# Light_SOT32.net
KiCad netlist of a schematic drawn in EAGLE
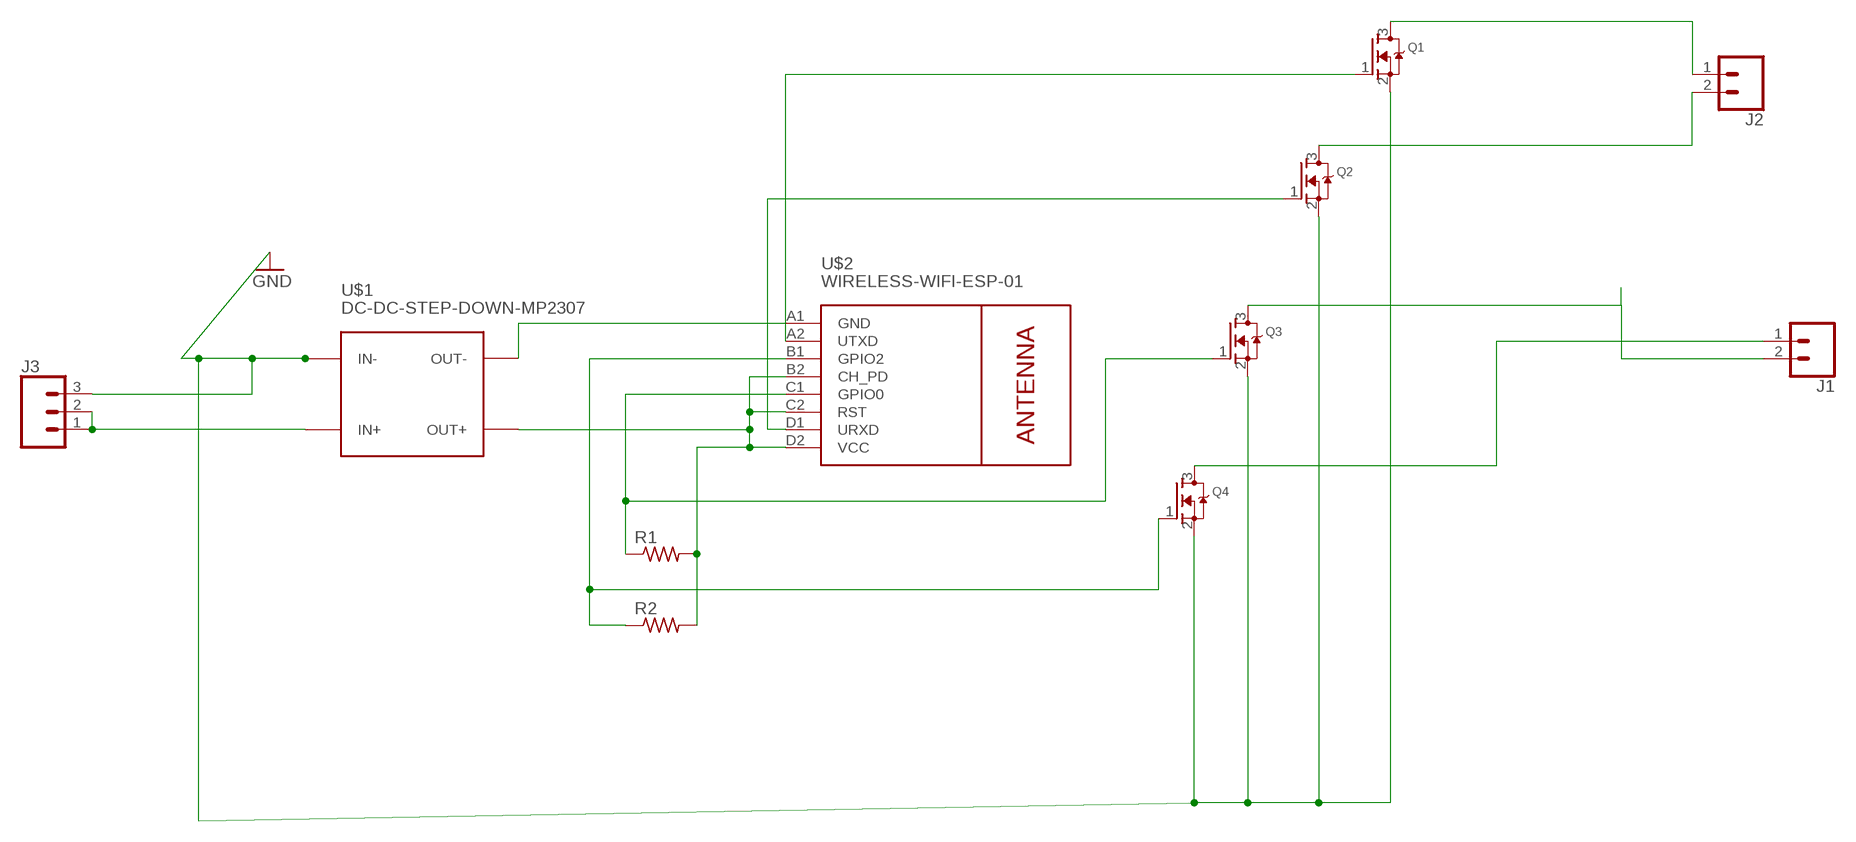
[diagram p0: schematic, sheet 1]

(export (version "E")
  (design (tool "Eeschema 10.0.6"))
  (components
    (comp (ref "J1")
      (value "CONN_023.5MM")
      (footprint "eagle-import:SCREWTERMINAL-3.5MM-2")
      (libsource (lib "eagle-import") (part "CONN_023.5MM"))
    )
    (comp (ref "J2")
      (value "CONN_023.5MM")
      (footprint "eagle-import:SCREWTERMINAL-3.5MM-2")
      (libsource (lib "eagle-import") (part "CONN_023.5MM"))
    )
    (comp (ref "J3")
      (value "CONN_03SCREW")
      (footprint "eagle-import:SCREWTERMINAL-3.5MM-3")
      (libsource (lib "eagle-import") (part "CONN_03SCREW"))
    )
    (comp (ref "Q1")
      (value "MOSFET-NREFLOW")
      (footprint "eagle-import:SOT23")
      (libsource (lib "eagle-import") (part "MOSFET-NREFLOW"))
    )
    (comp (ref "Q2")
      (value "MOSFET-NREFLOW")
      (footprint "eagle-import:SOT23")
      (libsource (lib "eagle-import") (part "MOSFET-NREFLOW"))
    )
    (comp (ref "Q3")
      (value "MOSFET-NREFLOW")
      (footprint "eagle-import:SOT23")
      (libsource (lib "eagle-import") (part "MOSFET-NREFLOW"))
    )
    (comp (ref "Q4")
      (value "MOSFET-NREFLOW")
      (footprint "eagle-import:SOT23")
      (libsource (lib "eagle-import") (part "MOSFET-NREFLOW"))
    )
    (comp (ref "R1")
      (value "R-US_R0805")
      (footprint "eagle-import:R0805")
      (libsource (lib "eagle-import") (part "R-US_R0805"))
    )
    (comp (ref "R2")
      (value "R-US_R0805")
      (footprint "eagle-import:R0805")
      (libsource (lib "eagle-import") (part "R-US_R0805"))
    )
    (comp (ref "U$1")
      (value "DC-DC-STEP-DOWN-MP2307")
      (footprint "eagle-import:DC-DC-STEP-DOWN-MP2307")
      (libsource (lib "eagle-import") (part "DC-DC-STEP-DOWN-MP2307"))
    )
    (comp (ref "U$2")
      (value "WIRELESS-WIFI-ESP-01")
      (footprint "eagle-import:WIRELESS-WIFI-ESP-01")
      (fields (field (name "SPICEPREFIX") "X"))
      (libsource (lib "eagle-import") (part "WIRELESS-WIFI-ESP-01"))
    )
  )
  (nets
    (net (code "1") (name "GND") (class "Default")
      (node (ref "J3") (pin "3") (pinfunction "3_3") (pintype "passive"))
      (node (ref "Q1") (pin "2") (pinfunction "S_2") (pintype "bidirectional"))
      (node (ref "Q2") (pin "2") (pinfunction "S_2") (pintype "bidirectional"))
      (node (ref "Q3") (pin "2") (pinfunction "S_2") (pintype "bidirectional"))
      (node (ref "Q4") (pin "2") (pinfunction "S_2") (pintype "bidirectional"))
      (node (ref "U$1") (pin "IN-") (pinfunction "IN-_IN-") (pintype "bidirectional"))
    )
    (net (code "2") (name "Net-(J3-Pad1)") (class "Default")
      (node (ref "J3") (pin "1") (pinfunction "1_1") (pintype "passive"))
      (node (ref "J3") (pin "2") (pinfunction "2_2") (pintype "passive"))
      (node (ref "U$1") (pin "IN+") (pinfunction "IN+_IN+") (pintype "bidirectional"))
    )
    (net (code "3") (name "Net-(Q1-D)") (class "Default")
      (node (ref "J2") (pin "1") (pinfunction "1_1") (pintype "passive"))
      (node (ref "Q1") (pin "3") (pinfunction "D_3") (pintype "bidirectional"))
    )
    (net (code "4") (name "Net-(Q1-G)") (class "Default")
      (node (ref "Q1") (pin "1") (pinfunction "G_1") (pintype "bidirectional"))
      (node (ref "U$2") (pin "A2") (pinfunction "UTXD_A2") (pintype "bidirectional"))
    )
    (net (code "5") (name "Net-(Q2-D)") (class "Default")
      (node (ref "J2") (pin "2") (pinfunction "2_2") (pintype "passive"))
      (node (ref "Q2") (pin "3") (pinfunction "D_3") (pintype "bidirectional"))
    )
    (net (code "6") (name "Net-(Q2-G)") (class "Default")
      (node (ref "Q2") (pin "1") (pinfunction "G_1") (pintype "bidirectional"))
      (node (ref "U$2") (pin "D1") (pinfunction "URXD_D1") (pintype "bidirectional"))
    )
    (net (code "7") (name "Net-(Q3-D)") (class "Default")
      (node (ref "J1") (pin "2") (pinfunction "2_2") (pintype "passive"))
      (node (ref "Q3") (pin "3") (pinfunction "D_3") (pintype "bidirectional"))
    )
    (net (code "8") (name "Net-(Q3-G)") (class "Default")
      (node (ref "Q3") (pin "1") (pinfunction "G_1") (pintype "bidirectional"))
      (node (ref "R1") (pin "1") (pinfunction "1_1") (pintype "passive"))
      (node (ref "U$2") (pin "C1") (pinfunction "GPIO0_C1") (pintype "bidirectional"))
    )
    (net (code "9") (name "Net-(Q4-D)") (class "Default")
      (node (ref "J1") (pin "1") (pinfunction "1_1") (pintype "passive"))
      (node (ref "Q4") (pin "3") (pinfunction "D_3") (pintype "bidirectional"))
    )
    (net (code "10") (name "Net-(Q4-G)") (class "Default")
      (node (ref "Q4") (pin "1") (pinfunction "G_1") (pintype "bidirectional"))
      (node (ref "R2") (pin "1") (pinfunction "1_1") (pintype "passive"))
      (node (ref "U$2") (pin "B1") (pinfunction "GPIO2_B1") (pintype "bidirectional"))
    )
    (net (code "11") (name "Net-(U$2-CH_PD)") (class "Default")
      (node (ref "R1") (pin "2") (pinfunction "2_2") (pintype "passive"))
      (node (ref "R2") (pin "2") (pinfunction "2_2") (pintype "passive"))
      (node (ref "U$1") (pin "OUT+") (pinfunction "OUT+_OUT+") (pintype "bidirectional"))
      (node (ref "U$2") (pin "B2") (pinfunction "CH_PD_B2") (pintype "bidirectional"))
      (node (ref "U$2") (pin "C2") (pinfunction "RST_C2") (pintype "bidirectional"))
      (node (ref "U$2") (pin "D2") (pinfunction "VCC_D2") (pintype "power_in"))
    )
    (net (code "12") (name "Net-(U$2-GND)") (class "Default")
      (node (ref "U$1") (pin "OUT-") (pinfunction "OUT-_OUT-") (pintype "bidirectional"))
      (node (ref "U$2") (pin "A1") (pinfunction "GND_A1") (pintype "power_in"))
    )
  )
)
